# LedBoatController.net
KiCad netlist of a schematic drawn in EAGLE
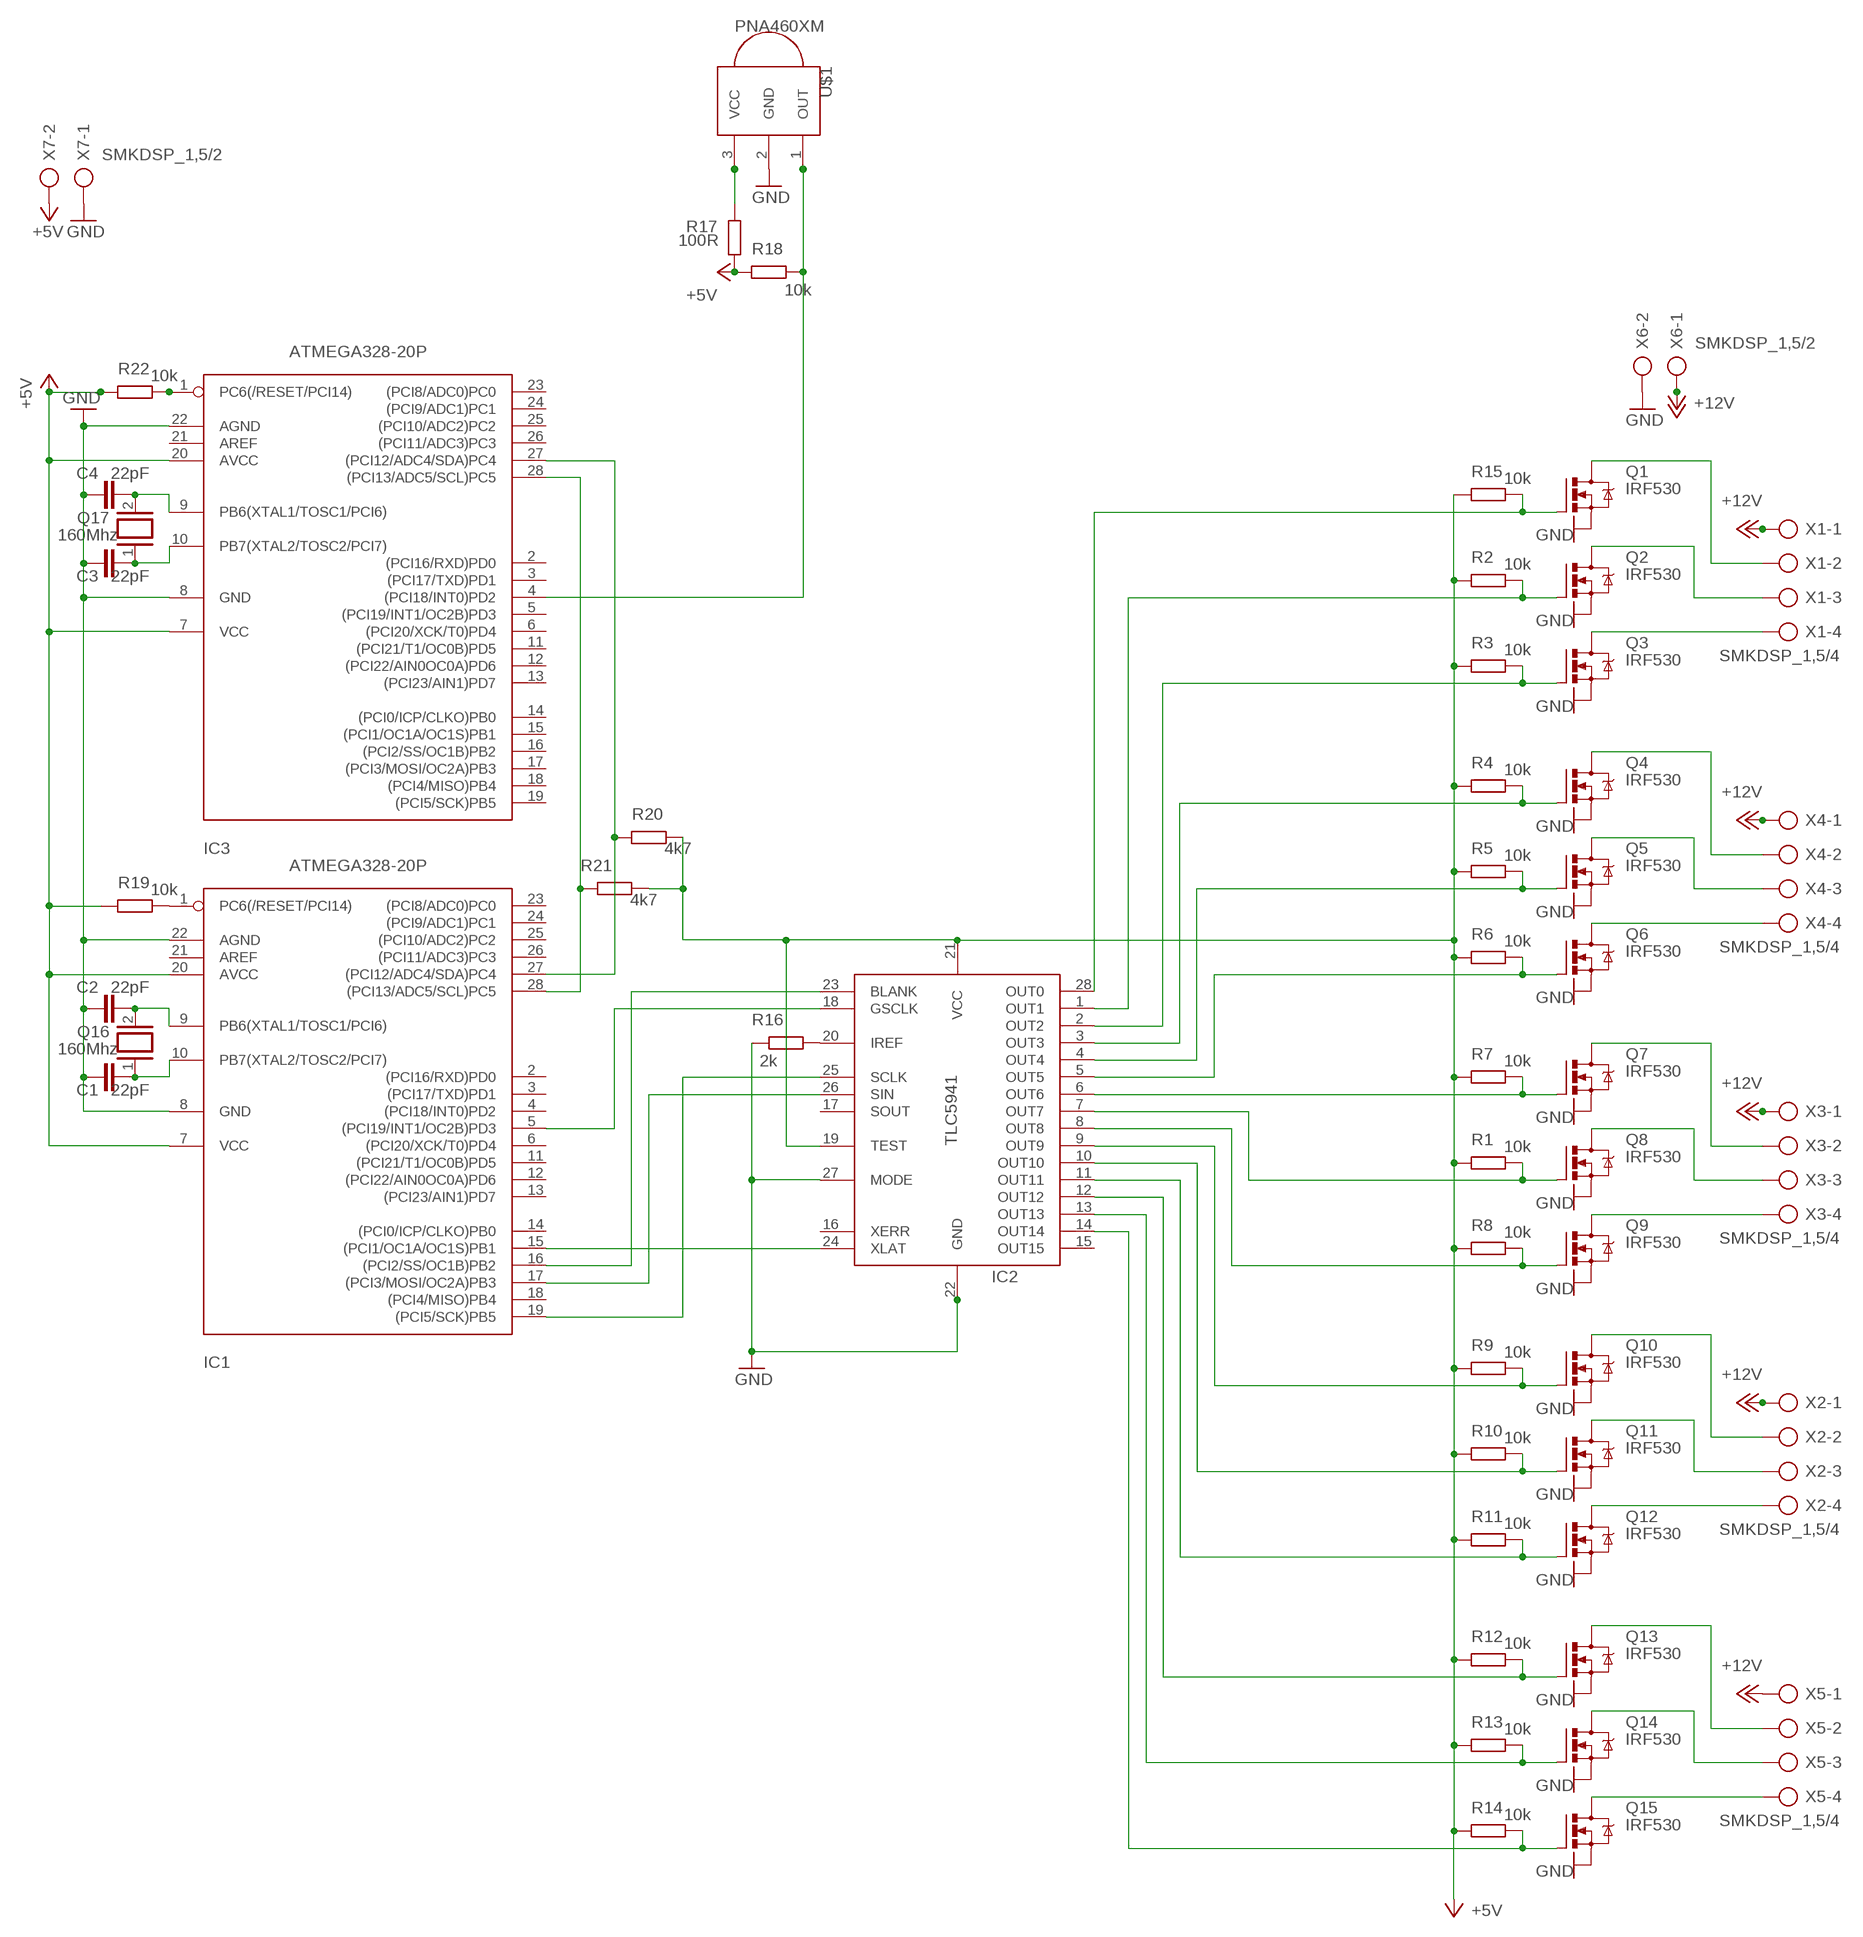
[diagram p0: schematic, sheet 1]

(export (version "E")
  (design (tool "Eeschema 10.0.6"))
  (components
    (comp (ref "C1")
      (value "22pF")
      (footprint "eagle-import:CAP-PTH-2.54")
      (libsource (lib "eagle-import") (part "22PF-PTH-2.54MM-200V-5%"))
    )
    (comp (ref "C2")
      (value "22pF")
      (footprint "eagle-import:CAP-PTH-2.54")
      (libsource (lib "eagle-import") (part "22PF-PTH-2.54MM-200V-5%"))
    )
    (comp (ref "C3")
      (value "22pF")
      (footprint "eagle-import:CAP-PTH-2.54")
      (libsource (lib "eagle-import") (part "22PF-PTH-2.54MM-200V-5%"))
    )
    (comp (ref "C4")
      (value "22pF")
      (footprint "eagle-import:CAP-PTH-2.54")
      (libsource (lib "eagle-import") (part "22PF-PTH-2.54MM-200V-5%"))
    )
    (comp (ref "IC1")
      (value "ATMEGA328-20P")
      (footprint "eagle-import:DIL28-3")
      (libsource (lib "eagle-import") (part "ATMEGA328P-20"))
    )
    (comp (ref "IC2")
      (value "TLC5941NT")
      (footprint "eagle-import:DIL28-3")
      (libsource (lib "eagle-import") (part "TLC5941NT"))
    )
    (comp (ref "IC3")
      (value "ATMEGA328-20P")
      (footprint "eagle-import:DIL28-3")
      (libsource (lib "eagle-import") (part "ATMEGA328P-20"))
    )
    (comp (ref "Q1")
      (value "IRF530")
      (footprint "eagle-import:TO220BV")
      (libsource (lib "eagle-import") (part "IRF530"))
    )
    (comp (ref "Q2")
      (value "IRF530")
      (footprint "eagle-import:TO220BV")
      (libsource (lib "eagle-import") (part "IRF530"))
    )
    (comp (ref "Q3")
      (value "IRF530")
      (footprint "eagle-import:TO220BV")
      (libsource (lib "eagle-import") (part "IRF530"))
    )
    (comp (ref "Q4")
      (value "IRF530")
      (footprint "eagle-import:TO220BV")
      (libsource (lib "eagle-import") (part "IRF530"))
    )
    (comp (ref "Q5")
      (value "IRF530")
      (footprint "eagle-import:TO220BV")
      (libsource (lib "eagle-import") (part "IRF530"))
    )
    (comp (ref "Q6")
      (value "IRF530")
      (footprint "eagle-import:TO220BV")
      (libsource (lib "eagle-import") (part "IRF530"))
    )
    (comp (ref "Q7")
      (value "IRF530")
      (footprint "eagle-import:TO220BV")
      (libsource (lib "eagle-import") (part "IRF530"))
    )
    (comp (ref "Q8")
      (value "IRF530")
      (footprint "eagle-import:TO220BV")
      (libsource (lib "eagle-import") (part "IRF530"))
    )
    (comp (ref "Q9")
      (value "IRF530")
      (footprint "eagle-import:TO220BV")
      (libsource (lib "eagle-import") (part "IRF530"))
    )
    (comp (ref "Q10")
      (value "IRF530")
      (footprint "eagle-import:TO220BV")
      (libsource (lib "eagle-import") (part "IRF530"))
    )
    (comp (ref "Q11")
      (value "IRF530")
      (footprint "eagle-import:TO220BV")
      (libsource (lib "eagle-import") (part "IRF530"))
    )
    (comp (ref "Q12")
      (value "IRF530")
      (footprint "eagle-import:TO220BV")
      (libsource (lib "eagle-import") (part "IRF530"))
    )
    (comp (ref "Q13")
      (value "IRF530")
      (footprint "eagle-import:TO220BV")
      (libsource (lib "eagle-import") (part "IRF530"))
    )
    (comp (ref "Q14")
      (value "IRF530")
      (footprint "eagle-import:TO220BV")
      (libsource (lib "eagle-import") (part "IRF530"))
    )
    (comp (ref "Q15")
      (value "IRF530")
      (footprint "eagle-import:TO220BV")
      (libsource (lib "eagle-import") (part "IRF530"))
    )
    (comp (ref "Q16")
      (value "160Mhz")
      (footprint "eagle-import:QS")
      (libsource (lib "eagle-import") (part "XTAL/S"))
    )
    (comp (ref "Q17")
      (value "160Mhz")
      (footprint "eagle-import:QS")
      (libsource (lib "eagle-import") (part "XTAL/S"))
    )
    (comp (ref "R1")
      (value "10k")
      (footprint "eagle-import:0207_10")
      (libsource (lib "eagle-import") (part "R-EU_0207/10"))
    )
    (comp (ref "R2")
      (value "10k")
      (footprint "eagle-import:0207_10")
      (libsource (lib "eagle-import") (part "R-EU_0207/10"))
    )
    (comp (ref "R3")
      (value "10k")
      (footprint "eagle-import:0207_10")
      (libsource (lib "eagle-import") (part "R-EU_0207/10"))
    )
    (comp (ref "R4")
      (value "10k")
      (footprint "eagle-import:0207_10")
      (libsource (lib "eagle-import") (part "R-EU_0207/10"))
    )
    (comp (ref "R5")
      (value "10k")
      (footprint "eagle-import:0207_10")
      (libsource (lib "eagle-import") (part "R-EU_0207/10"))
    )
    (comp (ref "R6")
      (value "10k")
      (footprint "eagle-import:0207_10")
      (libsource (lib "eagle-import") (part "R-EU_0207/10"))
    )
    (comp (ref "R7")
      (value "10k")
      (footprint "eagle-import:0207_10")
      (libsource (lib "eagle-import") (part "R-EU_0207/10"))
    )
    (comp (ref "R8")
      (value "10k")
      (footprint "eagle-import:0207_10")
      (libsource (lib "eagle-import") (part "R-EU_0207/10"))
    )
    (comp (ref "R9")
      (value "10k")
      (footprint "eagle-import:0207_10")
      (libsource (lib "eagle-import") (part "R-EU_0207/10"))
    )
    (comp (ref "R10")
      (value "10k")
      (footprint "eagle-import:0207_10")
      (libsource (lib "eagle-import") (part "R-EU_0207/10"))
    )
    (comp (ref "R11")
      (value "10k")
      (footprint "eagle-import:0207_10")
      (libsource (lib "eagle-import") (part "R-EU_0207/10"))
    )
    (comp (ref "R12")
      (value "10k")
      (footprint "eagle-import:0207_10")
      (libsource (lib "eagle-import") (part "R-EU_0207/10"))
    )
    (comp (ref "R13")
      (value "10k")
      (footprint "eagle-import:0207_10")
      (libsource (lib "eagle-import") (part "R-EU_0207/10"))
    )
    (comp (ref "R14")
      (value "10k")
      (footprint "eagle-import:0207_10")
      (libsource (lib "eagle-import") (part "R-EU_0207/10"))
    )
    (comp (ref "R15")
      (value "10k")
      (footprint "eagle-import:0207_10")
      (libsource (lib "eagle-import") (part "R-EU_0207/10"))
    )
    (comp (ref "R16")
      (value "2k")
      (footprint "eagle-import:0207_10")
      (libsource (lib "eagle-import") (part "R-EU_0207/10"))
    )
    (comp (ref "R17")
      (value "100R")
      (footprint "eagle-import:0207_10")
      (libsource (lib "eagle-import") (part "R-EU_0207/10"))
    )
    (comp (ref "R18")
      (value "10k")
      (footprint "eagle-import:0207_10")
      (libsource (lib "eagle-import") (part "R-EU_0207/10"))
    )
    (comp (ref "R19")
      (value "10k")
      (footprint "eagle-import:0207_10")
      (libsource (lib "eagle-import") (part "R-EU_0207/10"))
    )
    (comp (ref "R20")
      (value "4k7")
      (footprint "eagle-import:0207_10")
      (libsource (lib "eagle-import") (part "R-EU_0207/10"))
    )
    (comp (ref "R21")
      (value "4k7")
      (footprint "eagle-import:0207_10")
      (libsource (lib "eagle-import") (part "R-EU_0207/10"))
    )
    (comp (ref "R22")
      (value "10k")
      (footprint "eagle-import:0207_10")
      (libsource (lib "eagle-import") (part "R-EU_0207/10"))
    )
    (comp (ref "U$1")
      (value "PNA460XM")
      (footprint "eagle-import:PNA460XM")
      (libsource (lib "eagle-import") (part "PNA460XM"))
    )
    (comp (ref "X1")
      (value "SMKDSP_1,5/4")
      (footprint "eagle-import:SMKDSP_1,5_4")
      (fields (field (name "MF") "FARNELL") (field (name "MPN") "1733596"))
      (libsource (lib "eagle-import") (part "SMKDSP_1,5/4"))
    )
    (comp (ref "X2")
      (value "SMKDSP_1,5/4")
      (footprint "eagle-import:SMKDSP_1,5_4")
      (fields (field (name "MF") "FARNELL") (field (name "MPN") "1733596"))
      (libsource (lib "eagle-import") (part "SMKDSP_1,5/4"))
    )
    (comp (ref "X3")
      (value "SMKDSP_1,5/4")
      (footprint "eagle-import:SMKDSP_1,5_4")
      (fields (field (name "MF") "FARNELL") (field (name "MPN") "1733596"))
      (libsource (lib "eagle-import") (part "SMKDSP_1,5/4"))
    )
    (comp (ref "X4")
      (value "SMKDSP_1,5/4")
      (footprint "eagle-import:SMKDSP_1,5_4")
      (fields (field (name "MF") "FARNELL") (field (name "MPN") "1733596"))
      (libsource (lib "eagle-import") (part "SMKDSP_1,5/4"))
    )
    (comp (ref "X5")
      (value "SMKDSP_1,5/4")
      (footprint "eagle-import:SMKDSP_1,5_4")
      (fields (field (name "MF") "FARNELL") (field (name "MPN") "1733596"))
      (libsource (lib "eagle-import") (part "SMKDSP_1,5/4"))
    )
    (comp (ref "X6")
      (value "SMKDSP_1,5/2")
      (footprint "eagle-import:SMKDSP_1,5_2")
      (fields (field (name "MF") "FARNELL") (field (name "MPN") "1733570"))
      (libsource (lib "eagle-import") (part "SMKDSP_1,5/2"))
    )
    (comp (ref "X7")
      (value "SMKDSP_1,5/2")
      (footprint "eagle-import:SMKDSP_1,5_2")
      (fields (field (name "MF") "FARNELL") (field (name "MPN") "1733570"))
      (libsource (lib "eagle-import") (part "SMKDSP_1,5/2"))
    )
  )
  (nets
    (net (code "1") (name "+5V") (class "Default")
      (node (ref "IC1") (pin "20") (pinfunction "AVCC_20") (pintype "bidirectional"))
      (node (ref "IC1") (pin "7") (pinfunction "VCC_7") (pintype "bidirectional"))
      (node (ref "IC2") (pin "19") (pinfunction "TEST_19") (pintype "input"))
      (node (ref "IC2") (pin "21") (pinfunction "VCC_21") (pintype "power_in"))
      (node (ref "IC3") (pin "20") (pinfunction "AVCC_20") (pintype "bidirectional"))
      (node (ref "IC3") (pin "7") (pinfunction "VCC_7") (pintype "bidirectional"))
      (node (ref "R1") (pin "2") (pinfunction "2_2") (pintype "passive"))
      (node (ref "R10") (pin "2") (pinfunction "2_2") (pintype "passive"))
      (node (ref "R11") (pin "2") (pinfunction "2_2") (pintype "passive"))
      (node (ref "R12") (pin "2") (pinfunction "2_2") (pintype "passive"))
      (node (ref "R13") (pin "2") (pinfunction "2_2") (pintype "passive"))
      (node (ref "R14") (pin "2") (pinfunction "2_2") (pintype "passive"))
      (node (ref "R15") (pin "2") (pinfunction "2_2") (pintype "passive"))
      (node (ref "R17") (pin "2") (pinfunction "2_2") (pintype "passive"))
      (node (ref "R18") (pin "2") (pinfunction "2_2") (pintype "passive"))
      (node (ref "R19") (pin "2") (pinfunction "2_2") (pintype "passive"))
      (node (ref "R2") (pin "2") (pinfunction "2_2") (pintype "passive"))
      (node (ref "R20") (pin "2") (pinfunction "2_2") (pintype "passive"))
      (node (ref "R21") (pin "2") (pinfunction "2_2") (pintype "passive"))
      (node (ref "R22") (pin "2") (pinfunction "2_2") (pintype "passive"))
      (node (ref "R3") (pin "2") (pinfunction "2_2") (pintype "passive"))
      (node (ref "R4") (pin "2") (pinfunction "2_2") (pintype "passive"))
      (node (ref "R5") (pin "2") (pinfunction "2_2") (pintype "passive"))
      (node (ref "R6") (pin "2") (pinfunction "2_2") (pintype "passive"))
      (node (ref "R7") (pin "2") (pinfunction "2_2") (pintype "passive"))
      (node (ref "R8") (pin "2") (pinfunction "2_2") (pintype "passive"))
      (node (ref "R9") (pin "2") (pinfunction "2_2") (pintype "passive"))
      (node (ref "X7") (pin "2") (pinfunction "KL_2") (pintype "passive"))
    )
    (net (code "2") (name "+12V") (class "Default")
      (node (ref "X1") (pin "1") (pinfunction "KL_1") (pintype "passive"))
      (node (ref "X2") (pin "1") (pinfunction "KL_1") (pintype "passive"))
      (node (ref "X3") (pin "1") (pinfunction "KL_1") (pintype "passive"))
      (node (ref "X4") (pin "1") (pinfunction "KL_1") (pintype "passive"))
      (node (ref "X5") (pin "1") (pinfunction "KL_1") (pintype "passive"))
      (node (ref "X6") (pin "1") (pinfunction "KL_1") (pintype "passive"))
    )
    (net (code "3") (name "GND") (class "Default")
      (node (ref "C1") (pin "1") (pinfunction "1_1") (pintype "passive"))
      (node (ref "C2") (pin "1") (pinfunction "1_1") (pintype "passive"))
      (node (ref "C3") (pin "1") (pinfunction "1_1") (pintype "passive"))
      (node (ref "C4") (pin "1") (pinfunction "1_1") (pintype "passive"))
      (node (ref "IC1") (pin "22") (pinfunction "AGND_22") (pintype "bidirectional"))
      (node (ref "IC1") (pin "8") (pinfunction "GND_8") (pintype "bidirectional"))
      (node (ref "IC2") (pin "22") (pinfunction "GND_22") (pintype "power_in"))
      (node (ref "IC2") (pin "27") (pinfunction "MODE_27") (pintype "input"))
      (node (ref "IC3") (pin "22") (pinfunction "AGND_22") (pintype "bidirectional"))
      (node (ref "IC3") (pin "8") (pinfunction "GND_8") (pintype "bidirectional"))
      (node (ref "Q1") (pin "S") (pinfunction "S_S") (pintype "passive"))
      (node (ref "Q10") (pin "S") (pinfunction "S_S") (pintype "passive"))
      (node (ref "Q11") (pin "S") (pinfunction "S_S") (pintype "passive"))
      (node (ref "Q12") (pin "S") (pinfunction "S_S") (pintype "passive"))
      (node (ref "Q13") (pin "S") (pinfunction "S_S") (pintype "passive"))
      (node (ref "Q14") (pin "S") (pinfunction "S_S") (pintype "passive"))
      (node (ref "Q15") (pin "S") (pinfunction "S_S") (pintype "passive"))
      (node (ref "Q2") (pin "S") (pinfunction "S_S") (pintype "passive"))
      (node (ref "Q3") (pin "S") (pinfunction "S_S") (pintype "passive"))
      (node (ref "Q4") (pin "S") (pinfunction "S_S") (pintype "passive"))
      (node (ref "Q5") (pin "S") (pinfunction "S_S") (pintype "passive"))
      (node (ref "Q6") (pin "S") (pinfunction "S_S") (pintype "passive"))
      (node (ref "Q7") (pin "S") (pinfunction "S_S") (pintype "passive"))
      (node (ref "Q8") (pin "S") (pinfunction "S_S") (pintype "passive"))
      (node (ref "Q9") (pin "S") (pinfunction "S_S") (pintype "passive"))
      (node (ref "R16") (pin "2") (pinfunction "2_2") (pintype "passive"))
      (node (ref "U$1") (pin "2") (pinfunction "GND_2") (pintype "power_in"))
      (node (ref "X6") (pin "2") (pinfunction "KL_2") (pintype "passive"))
      (node (ref "X7") (pin "1") (pinfunction "KL_1") (pintype "passive"))
    )
    (net (code "4") (name "Net-(IC1-(PCI1{slash}OC1A{slash}OC1S)PB1)") (class "Default")
      (node (ref "IC1") (pin "15") (pinfunction "(PCI1/OC1A/OC1S)PB1_15") (pintype "bidirectional"))
      (node (ref "IC2") (pin "24") (pinfunction "XLAT_24") (pintype "input"))
    )
    (net (code "5") (name "Net-(IC1-(PCI2{slash}SS{slash}OC1B)PB2)") (class "Default")
      (node (ref "IC1") (pin "16") (pinfunction "(PCI2/SS/OC1B)PB2_16") (pintype "bidirectional"))
      (node (ref "IC2") (pin "23") (pinfunction "BLANK_23") (pintype "input"))
    )
    (net (code "6") (name "Net-(IC1-(PCI3{slash}MOSI{slash}OC2A)PB3)") (class "Default")
      (node (ref "IC1") (pin "17") (pinfunction "(PCI3/MOSI/OC2A)PB3_17") (pintype "bidirectional"))
      (node (ref "IC2") (pin "26") (pinfunction "SIN_26") (pintype "input"))
    )
    (net (code "7") (name "Net-(IC1-(PCI5{slash}SCK)PB5)") (class "Default")
      (node (ref "IC1") (pin "19") (pinfunction "(PCI5/SCK)PB5_19") (pintype "bidirectional"))
      (node (ref "IC2") (pin "25") (pinfunction "SCLK_25") (pintype "input"))
    )
    (net (code "8") (name "Net-(IC1-(PCI12{slash}ADC4{slash}SDA)PC4)") (class "Default")
      (node (ref "IC1") (pin "27") (pinfunction "(PCI12/ADC4/SDA)PC4_27") (pintype "bidirectional"))
      (node (ref "IC3") (pin "27") (pinfunction "(PCI12/ADC4/SDA)PC4_27") (pintype "bidirectional"))
      (node (ref "R20") (pin "1") (pinfunction "1_1") (pintype "passive"))
    )
    (net (code "9") (name "Net-(IC1-(PCI13{slash}ADC5{slash}SCL)PC5)") (class "Default")
      (node (ref "IC1") (pin "28") (pinfunction "(PCI13/ADC5/SCL)PC5_28") (pintype "bidirectional"))
      (node (ref "IC3") (pin "28") (pinfunction "(PCI13/ADC5/SCL)PC5_28") (pintype "bidirectional"))
      (node (ref "R21") (pin "1") (pinfunction "1_1") (pintype "passive"))
    )
    (net (code "10") (name "Net-(IC1-(PCI19{slash}INT1{slash}OC2B)PD3)") (class "Default")
      (node (ref "IC1") (pin "5") (pinfunction "(PCI19/INT1/OC2B)PD3_5") (pintype "bidirectional"))
      (node (ref "IC2") (pin "18") (pinfunction "GSCLK_18") (pintype "input"))
    )
    (net (code "11") (name "Net-(IC1-PB6(XTAL1{slash}TOSC1{slash}PCI6))") (class "Default")
      (node (ref "C2") (pin "2") (pinfunction "2_2") (pintype "passive"))
      (node (ref "IC1") (pin "9") (pinfunction "PB6(XTAL1/TOSC1/PCI6)_9") (pintype "bidirectional"))
      (node (ref "Q16") (pin "2") (pinfunction "2_2") (pintype "passive"))
    )
    (net (code "12") (name "Net-(IC1-PB7(XTAL2{slash}TOSC2{slash}PCI7))") (class "Default")
      (node (ref "C1") (pin "2") (pinfunction "2_2") (pintype "passive"))
      (node (ref "IC1") (pin "10") (pinfunction "PB7(XTAL2/TOSC2/PCI7)_10") (pintype "bidirectional"))
      (node (ref "Q16") (pin "1") (pinfunction "1_1") (pintype "passive"))
    )
    (net (code "13") (name "Net-(IC1-PC6({slash}RESET{slash}PCI14))") (class "Default")
      (node (ref "IC1") (pin "1") (pinfunction "PC6(/RESET/PCI14)_1") (pintype "bidirectional"))
      (node (ref "R19") (pin "1") (pinfunction "1_1") (pintype "passive"))
    )
    (net (code "14") (name "Net-(IC2-IREF)") (class "Default")
      (node (ref "IC2") (pin "20") (pinfunction "IREF_20") (pintype "bidirectional"))
      (node (ref "R16") (pin "1") (pinfunction "1_1") (pintype "passive"))
    )
    (net (code "15") (name "Net-(IC2-OUT0)") (class "Default")
      (node (ref "IC2") (pin "28") (pinfunction "OUT0_28") (pintype "output"))
      (node (ref "Q1") (pin "G") (pinfunction "G_G") (pintype "passive"))
      (node (ref "R15") (pin "1") (pinfunction "1_1") (pintype "passive"))
    )
    (net (code "16") (name "Net-(IC2-OUT1)") (class "Default")
      (node (ref "IC2") (pin "1") (pinfunction "OUT1_1") (pintype "output"))
      (node (ref "Q2") (pin "G") (pinfunction "G_G") (pintype "passive"))
      (node (ref "R2") (pin "1") (pinfunction "1_1") (pintype "passive"))
    )
    (net (code "17") (name "Net-(IC2-OUT2)") (class "Default")
      (node (ref "IC2") (pin "2") (pinfunction "OUT2_2") (pintype "output"))
      (node (ref "Q3") (pin "G") (pinfunction "G_G") (pintype "passive"))
      (node (ref "R3") (pin "1") (pinfunction "1_1") (pintype "passive"))
    )
    (net (code "18") (name "Net-(IC2-OUT3)") (class "Default")
      (node (ref "IC2") (pin "3") (pinfunction "OUT3_3") (pintype "output"))
      (node (ref "Q4") (pin "G") (pinfunction "G_G") (pintype "passive"))
      (node (ref "R4") (pin "1") (pinfunction "1_1") (pintype "passive"))
    )
    (net (code "19") (name "Net-(IC2-OUT4)") (class "Default")
      (node (ref "IC2") (pin "4") (pinfunction "OUT4_4") (pintype "output"))
      (node (ref "Q5") (pin "G") (pinfunction "G_G") (pintype "passive"))
      (node (ref "R5") (pin "1") (pinfunction "1_1") (pintype "passive"))
    )
    (net (code "20") (name "Net-(IC2-OUT5)") (class "Default")
      (node (ref "IC2") (pin "5") (pinfunction "OUT5_5") (pintype "output"))
      (node (ref "Q6") (pin "G") (pinfunction "G_G") (pintype "passive"))
      (node (ref "R6") (pin "1") (pinfunction "1_1") (pintype "passive"))
    )
    (net (code "21") (name "Net-(IC2-OUT6)") (class "Default")
      (node (ref "IC2") (pin "6") (pinfunction "OUT6_6") (pintype "output"))
      (node (ref "Q7") (pin "G") (pinfunction "G_G") (pintype "passive"))
      (node (ref "R7") (pin "1") (pinfunction "1_1") (pintype "passive"))
    )
    (net (code "22") (name "Net-(IC2-OUT7)") (class "Default")
      (node (ref "IC2") (pin "7") (pinfunction "OUT7_7") (pintype "output"))
      (node (ref "Q8") (pin "G") (pinfunction "G_G") (pintype "passive"))
      (node (ref "R1") (pin "1") (pinfunction "1_1") (pintype "passive"))
    )
    (net (code "23") (name "Net-(IC2-OUT8)") (class "Default")
      (node (ref "IC2") (pin "8") (pinfunction "OUT8_8") (pintype "output"))
      (node (ref "Q9") (pin "G") (pinfunction "G_G") (pintype "passive"))
      (node (ref "R8") (pin "1") (pinfunction "1_1") (pintype "passive"))
    )
    (net (code "24") (name "Net-(IC2-OUT9)") (class "Default")
      (node (ref "IC2") (pin "9") (pinfunction "OUT9_9") (pintype "output"))
      (node (ref "Q10") (pin "G") (pinfunction "G_G") (pintype "passive"))
      (node (ref "R9") (pin "1") (pinfunction "1_1") (pintype "passive"))
    )
    (net (code "25") (name "Net-(IC2-OUT10)") (class "Default")
      (node (ref "IC2") (pin "10") (pinfunction "OUT10_10") (pintype "output"))
      (node (ref "Q11") (pin "G") (pinfunction "G_G") (pintype "passive"))
      (node (ref "R10") (pin "1") (pinfunction "1_1") (pintype "passive"))
    )
    (net (code "26") (name "Net-(IC2-OUT11)") (class "Default")
      (node (ref "IC2") (pin "11") (pinfunction "OUT11_11") (pintype "output"))
      (node (ref "Q12") (pin "G") (pinfunction "G_G") (pintype "passive"))
      (node (ref "R11") (pin "1") (pinfunction "1_1") (pintype "passive"))
    )
    (net (code "27") (name "Net-(IC2-OUT12)") (class "Default")
      (node (ref "IC2") (pin "12") (pinfunction "OUT12_12") (pintype "output"))
      (node (ref "Q13") (pin "G") (pinfunction "G_G") (pintype "passive"))
      (node (ref "R12") (pin "1") (pinfunction "1_1") (pintype "passive"))
    )
    (net (code "28") (name "Net-(IC2-OUT13)") (class "Default")
      (node (ref "IC2") (pin "13") (pinfunction "OUT13_13") (pintype "output"))
      (node (ref "Q14") (pin "G") (pinfunction "G_G") (pintype "passive"))
      (node (ref "R13") (pin "1") (pinfunction "1_1") (pintype "passive"))
    )
    (net (code "29") (name "Net-(IC2-OUT14)") (class "Default")
      (node (ref "IC2") (pin "14") (pinfunction "OUT14_14") (pintype "output"))
      (node (ref "Q15") (pin "G") (pinfunction "G_G") (pintype "passive"))
      (node (ref "R14") (pin "1") (pinfunction "1_1") (pintype "passive"))
    )
    (net (code "30") (name "Net-(IC3-(PCI18{slash}INT0)PD2)") (class "Default")
      (node (ref "IC3") (pin "4") (pinfunction "(PCI18/INT0)PD2_4") (pintype "bidirectional"))
      (node (ref "R18") (pin "1") (pinfunction "1_1") (pintype "passive"))
      (node (ref "U$1") (pin "1") (pinfunction "OUT_1") (pintype "output"))
    )
    (net (code "31") (name "Net-(IC3-PB6(XTAL1{slash}TOSC1{slash}PCI6))") (class "Default")
      (node (ref "C4") (pin "2") (pinfunction "2_2") (pintype "passive"))
      (node (ref "IC3") (pin "9") (pinfunction "PB6(XTAL1/TOSC1/PCI6)_9") (pintype "bidirectional"))
      (node (ref "Q17") (pin "2") (pinfunction "2_2") (pintype "passive"))
    )
    (net (code "32") (name "Net-(IC3-PB7(XTAL2{slash}TOSC2{slash}PCI7))") (class "Default")
      (node (ref "C3") (pin "2") (pinfunction "2_2") (pintype "passive"))
      (node (ref "IC3") (pin "10") (pinfunction "PB7(XTAL2/TOSC2/PCI7)_10") (pintype "bidirectional"))
      (node (ref "Q17") (pin "1") (pinfunction "1_1") (pintype "passive"))
    )
    (net (code "33") (name "Net-(IC3-PC6({slash}RESET{slash}PCI14))") (class "Default")
      (node (ref "IC3") (pin "1") (pinfunction "PC6(/RESET/PCI14)_1") (pintype "bidirectional"))
      (node (ref "R22") (pin "1") (pinfunction "1_1") (pintype "passive"))
    )
    (net (code "34") (name "Net-(U$1-VCC)") (class "Default")
      (node (ref "R17") (pin "1") (pinfunction "1_1") (pintype "passive"))
      (node (ref "U$1") (pin "3") (pinfunction "VCC_3") (pintype "power_in"))
    )
    (net (code "35") (name "Net-(X1B-KL)") (class "Default")
      (node (ref "Q1") (pin "D") (pinfunction "D_D") (pintype "passive"))
      (node (ref "X1") (pin "2") (pinfunction "KL_2") (pintype "passive"))
    )
    (net (code "36") (name "Net-(X1C-KL)") (class "Default")
      (node (ref "Q2") (pin "D") (pinfunction "D_D") (pintype "passive"))
      (node (ref "X1") (pin "3") (pinfunction "KL_3") (pintype "passive"))
    )
    (net (code "37") (name "Net-(X1D-KL)") (class "Default")
      (node (ref "Q3") (pin "D") (pinfunction "D_D") (pintype "passive"))
      (node (ref "X1") (pin "4") (pinfunction "KL_4") (pintype "passive"))
    )
    (net (code "38") (name "Net-(X2B-KL)") (class "Default")
      (node (ref "Q10") (pin "D") (pinfunction "D_D") (pintype "passive"))
      (node (ref "X2") (pin "2") (pinfunction "KL_2") (pintype "passive"))
    )
    (net (code "39") (name "Net-(X2C-KL)") (class "Default")
      (node (ref "Q11") (pin "D") (pinfunction "D_D") (pintype "passive"))
      (node (ref "X2") (pin "3") (pinfunction "KL_3") (pintype "passive"))
    )
    (net (code "40") (name "Net-(X2D-KL)") (class "Default")
      (node (ref "Q12") (pin "D") (pinfunction "D_D") (pintype "passive"))
      (node (ref "X2") (pin "4") (pinfunction "KL_4") (pintype "passive"))
    )
    (net (code "41") (name "Net-(X3B-KL)") (class "Default")
      (node (ref "Q7") (pin "D") (pinfunction "D_D") (pintype "passive"))
      (node (ref "X3") (pin "2") (pinfunction "KL_2") (pintype "passive"))
    )
    (net (code "42") (name "Net-(X3C-KL)") (class "Default")
      (node (ref "Q8") (pin "D") (pinfunction "D_D") (pintype "passive"))
      (node (ref "X3") (pin "3") (pinfunction "KL_3") (pintype "passive"))
    )
    (net (code "43") (name "Net-(X3D-KL)") (class "Default")
      (node (ref "Q9") (pin "D") (pinfunction "D_D") (pintype "passive"))
      (node (ref "X3") (pin "4") (pinfunction "KL_4") (pintype "passive"))
    )
    (net (code "44") (name "Net-(X4B-KL)") (class "Default")
      (node (ref "Q4") (pin "D") (pinfunction "D_D") (pintype "passive"))
      (node (ref "X4") (pin "2") (pinfunction "KL_2") (pintype "passive"))
    )
    (net (code "45") (name "Net-(X4C-KL)") (class "Default")
      (node (ref "Q5") (pin "D") (pinfunction "D_D") (pintype "passive"))
      (node (ref "X4") (pin "3") (pinfunction "KL_3") (pintype "passive"))
    )
    (net (code "46") (name "Net-(X4D-KL)") (class "Default")
      (node (ref "Q6") (pin "D") (pinfunction "D_D") (pintype "passive"))
      (node (ref "X4") (pin "4") (pinfunction "KL_4") (pintype "passive"))
    )
    (net (code "47") (name "Net-(X5B-KL)") (class "Default")
      (node (ref "Q13") (pin "D") (pinfunction "D_D") (pintype "passive"))
      (node (ref "X5") (pin "2") (pinfunction "KL_2") (pintype "passive"))
    )
    (net (code "48") (name "Net-(X5C-KL)") (class "Default")
      (node (ref "Q14") (pin "D") (pinfunction "D_D") (pintype "passive"))
      (node (ref "X5") (pin "3") (pinfunction "KL_3") (pintype "passive"))
    )
    (net (code "49") (name "Net-(X5D-KL)") (class "Default")
      (node (ref "Q15") (pin "D") (pinfunction "D_D") (pintype "passive"))
      (node (ref "X5") (pin "4") (pinfunction "KL_4") (pintype "passive"))
    )
    (net (code "50") (name "unconnected-(IC1-(PCI0{slash}ICP{slash}CLKO)PB0-Pad14)") (class "Default")
      (node (ref "IC1") (pin "14") (pinfunction "(PCI0/ICP/CLKO)PB0_14") (pintype "bidirectional"))
    )
    (net (code "51") (name "unconnected-(IC1-(PCI4{slash}MISO)PB4-Pad18)") (class "Default")
      (node (ref "IC1") (pin "18") (pinfunction "(PCI4/MISO)PB4_18") (pintype "bidirectional"))
    )
    (net (code "52") (name "unconnected-(IC1-(PCI8{slash}ADC0)PC0-Pad23)") (class "Default")
      (node (ref "IC1") (pin "23") (pinfunction "(PCI8/ADC0)PC0_23") (pintype "bidirectional"))
    )
    (net (code "53") (name "unconnected-(IC1-(PCI9{slash}ADC1)PC1-Pad24)") (class "Default")
      (node (ref "IC1") (pin "24") (pinfunction "(PCI9/ADC1)PC1_24") (pintype "bidirectional"))
    )
    (net (code "54") (name "unconnected-(IC1-(PCI10{slash}ADC2)PC2-Pad25)") (class "Default")
      (node (ref "IC1") (pin "25") (pinfunction "(PCI10/ADC2)PC2_25") (pintype "bidirectional"))
    )
    (net (code "55") (name "unconnected-(IC1-(PCI11{slash}ADC3)PC3-Pad26)") (class "Default")
      (node (ref "IC1") (pin "26") (pinfunction "(PCI11/ADC3)PC3_26") (pintype "bidirectional"))
    )
    (net (code "56") (name "unconnected-(IC1-(PCI16{slash}RXD)PD0-Pad2)") (class "Default")
      (node (ref "IC1") (pin "2") (pinfunction "(PCI16/RXD)PD0_2") (pintype "bidirectional"))
    )
    (net (code "57") (name "unconnected-(IC1-(PCI17{slash}TXD)PD1-Pad3)") (class "Default")
      (node (ref "IC1") (pin "3") (pinfunction "(PCI17/TXD)PD1_3") (pintype "bidirectional"))
    )
    (net (code "58") (name "unconnected-(IC1-(PCI18{slash}INT0)PD2-Pad4)") (class "Default")
      (node (ref "IC1") (pin "4") (pinfunction "(PCI18/INT0)PD2_4") (pintype "bidirectional"))
    )
    (net (code "59") (name "unconnected-(IC1-(PCI20{slash}XCK{slash}T0)PD4-Pad6)") (class "Default")
      (node (ref "IC1") (pin "6") (pinfunction "(PCI20/XCK/T0)PD4_6") (pintype "bidirectional"))
    )
    (net (code "60") (name "unconnected-(IC1-(PCI21{slash}T1{slash}OC0B)PD5-Pad11)") (class "Default")
      (node (ref "IC1") (pin "11") (pinfunction "(PCI21/T1/OC0B)PD5_11") (pintype "bidirectional"))
    )
    (net (code "61") (name "unconnected-(IC1-(PCI22{slash}AIN0OC0A)PD6-Pad12)") (class "Default")
      (node (ref "IC1") (pin "12") (pinfunction "(PCI22/AIN0OC0A)PD6_12") (pintype "bidirectional"))
    )
    (net (code "62") (name "unconnected-(IC1-(PCI23{slash}AIN1)PD7-Pad13)") (class "Default")
      (node (ref "IC1") (pin "13") (pinfunction "(PCI23/AIN1)PD7_13") (pintype "bidirectional"))
    )
    (net (code "63") (name "unconnected-(IC1-AREF-Pad21)") (class "Default")
      (node (ref "IC1") (pin "21") (pinfunction "AREF_21") (pintype "bidirectional"))
    )
    (net (code "64") (name "unconnected-(IC2-OUT15-Pad15)") (class "Default")
      (node (ref "IC2") (pin "15") (pinfunction "OUT15_15") (pintype "output"))
    )
    (net (code "65") (name "unconnected-(IC2-SOUT-Pad17)") (class "Default")
      (node (ref "IC2") (pin "17") (pinfunction "SOUT_17") (pintype "output"))
    )
    (net (code "66") (name "unconnected-(IC2-XERR-Pad16)") (class "Default")
      (node (ref "IC2") (pin "16") (pinfunction "XERR_16") (pintype "output"))
    )
    (net (code "67") (name "unconnected-(IC3-(PCI0{slash}ICP{slash}CLKO)PB0-Pad14)") (class "Default")
      (node (ref "IC3") (pin "14") (pinfunction "(PCI0/ICP/CLKO)PB0_14") (pintype "bidirectional"))
    )
    (net (code "68") (name "unconnected-(IC3-(PCI1{slash}OC1A{slash}OC1S)PB1-Pad15)") (class "Default")
      (node (ref "IC3") (pin "15") (pinfunction "(PCI1/OC1A/OC1S)PB1_15") (pintype "bidirectional"))
    )
    (net (code "69") (name "unconnected-(IC3-(PCI2{slash}SS{slash}OC1B)PB2-Pad16)") (class "Default")
      (node (ref "IC3") (pin "16") (pinfunction "(PCI2/SS/OC1B)PB2_16") (pintype "bidirectional"))
    )
    (net (code "70") (name "unconnected-(IC3-(PCI3{slash}MOSI{slash}OC2A)PB3-Pad17)") (class "Default")
      (node (ref "IC3") (pin "17") (pinfunction "(PCI3/MOSI/OC2A)PB3_17") (pintype "bidirectional"))
    )
    (net (code "71") (name "unconnected-(IC3-(PCI4{slash}MISO)PB4-Pad18)") (class "Default")
      (node (ref "IC3") (pin "18") (pinfunction "(PCI4/MISO)PB4_18") (pintype "bidirectional"))
    )
    (net (code "72") (name "unconnected-(IC3-(PCI5{slash}SCK)PB5-Pad19)") (class "Default")
      (node (ref "IC3") (pin "19") (pinfunction "(PCI5/SCK)PB5_19") (pintype "bidirectional"))
    )
    (net (code "73") (name "unconnected-(IC3-(PCI8{slash}ADC0)PC0-Pad23)") (class "Default")
      (node (ref "IC3") (pin "23") (pinfunction "(PCI8/ADC0)PC0_23") (pintype "bidirectional"))
    )
    (net (code "74") (name "unconnected-(IC3-(PCI9{slash}ADC1)PC1-Pad24)") (class "Default")
      (node (ref "IC3") (pin "24") (pinfunction "(PCI9/ADC1)PC1_24") (pintype "bidirectional"))
    )
    (net (code "75") (name "unconnected-(IC3-(PCI10{slash}ADC2)PC2-Pad25)") (class "Default")
      (node (ref "IC3") (pin "25") (pinfunction "(PCI10/ADC2)PC2_25") (pintype "bidirectional"))
    )
    (net (code "76") (name "unconnected-(IC3-(PCI11{slash}ADC3)PC3-Pad26)") (class "Default")
      (node (ref "IC3") (pin "26") (pinfunction "(PCI11/ADC3)PC3_26") (pintype "bidirectional"))
    )
    (net (code "77") (name "unconnected-(IC3-(PCI16{slash}RXD)PD0-Pad2)") (class "Default")
      (node (ref "IC3") (pin "2") (pinfunction "(PCI16/RXD)PD0_2") (pintype "bidirectional"))
    )
    (net (code "78") (name "unconnected-(IC3-(PCI17{slash}TXD)PD1-Pad3)") (class "Default")
      (node (ref "IC3") (pin "3") (pinfunction "(PCI17/TXD)PD1_3") (pintype "bidirectional"))
    )
    (net (code "79") (name "unconnected-(IC3-(PCI19{slash}INT1{slash}OC2B)PD3-Pad5)") (class "Default")
      (node (ref "IC3") (pin "5") (pinfunction "(PCI19/INT1/OC2B)PD3_5") (pintype "bidirectional"))
    )
    (net (code "80") (name "unconnected-(IC3-(PCI20{slash}XCK{slash}T0)PD4-Pad6)") (class "Default")
      (node (ref "IC3") (pin "6") (pinfunction "(PCI20/XCK/T0)PD4_6") (pintype "bidirectional"))
    )
    (net (code "81") (name "unconnected-(IC3-(PCI21{slash}T1{slash}OC0B)PD5-Pad11)") (class "Default")
      (node (ref "IC3") (pin "11") (pinfunction "(PCI21/T1/OC0B)PD5_11") (pintype "bidirectional"))
    )
    (net (code "82") (name "unconnected-(IC3-(PCI22{slash}AIN0OC0A)PD6-Pad12)") (class "Default")
      (node (ref "IC3") (pin "12") (pinfunction "(PCI22/AIN0OC0A)PD6_12") (pintype "bidirectional"))
    )
    (net (code "83") (name "unconnected-(IC3-(PCI23{slash}AIN1)PD7-Pad13)") (class "Default")
      (node (ref "IC3") (pin "13") (pinfunction "(PCI23/AIN1)PD7_13") (pintype "bidirectional"))
    )
    (net (code "84") (name "unconnected-(IC3-AREF-Pad21)") (class "Default")
      (node (ref "IC3") (pin "21") (pinfunction "AREF_21") (pintype "bidirectional"))
    )
  )
)
